# mrf89-breakout.net
KiCad netlist of a schematic drawn in EAGLE
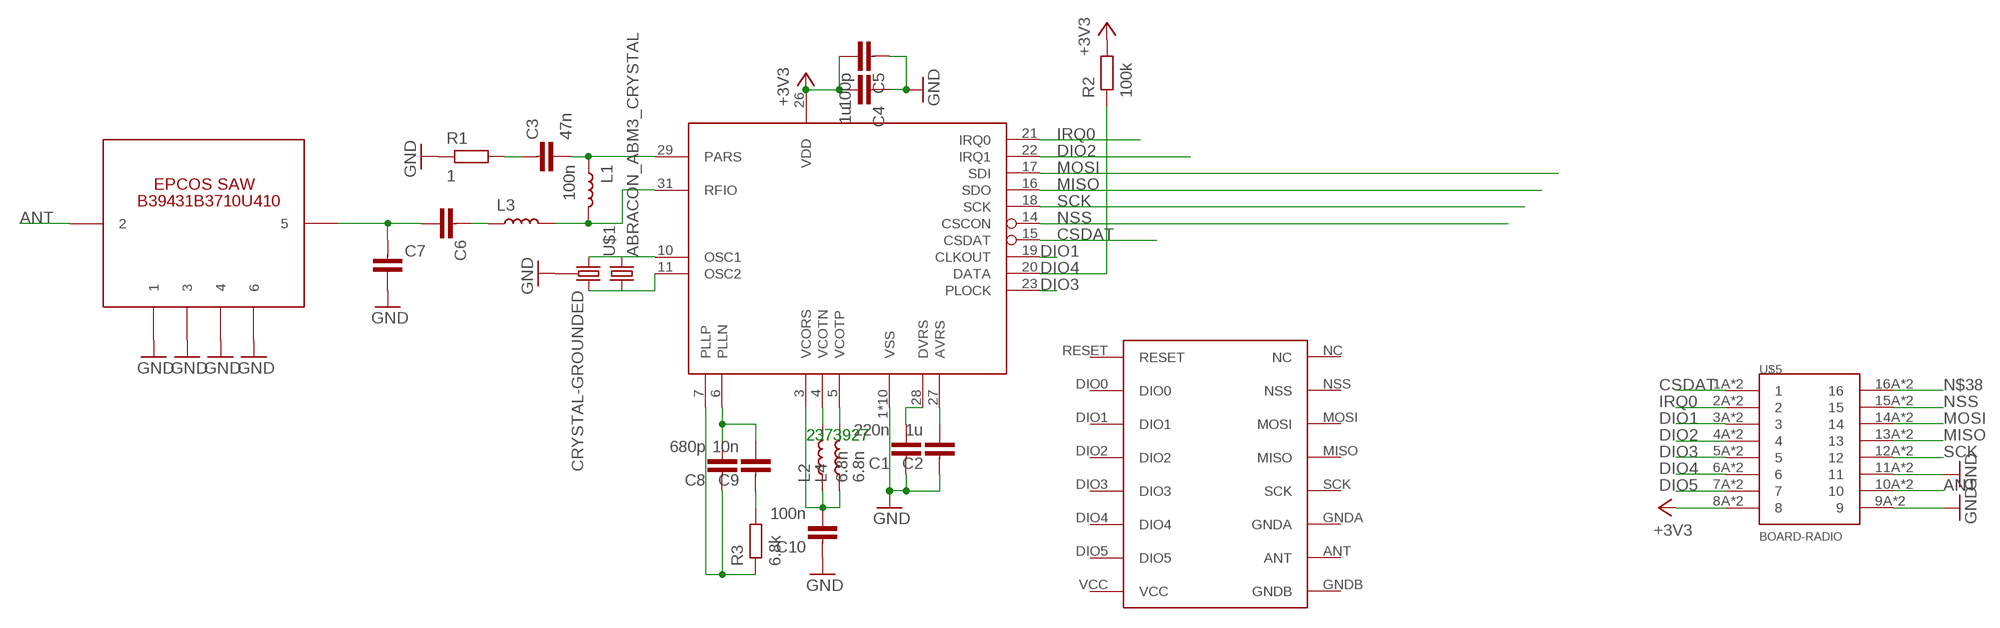
[diagram p0: schematic, sheet 1]

(export (version "E")
  (design (tool "Eeschema 10.0.6"))
  (components
    (comp (ref "C1")
      (value "220n")
      (footprint "eagle-import:C0603-N")
      (libsource (lib "eagle-import") (part "CAPACITOR0603-N"))
    )
    (comp (ref "C2")
      (value "1u")
      (footprint "eagle-import:C0603-N")
      (libsource (lib "eagle-import") (part "CAPACITOR0603-N"))
    )
    (comp (ref "C3")
      (value "47n")
      (footprint "eagle-import:C0603-N")
      (libsource (lib "eagle-import") (part "CAPACITOR0603-N"))
    )
    (comp (ref "C4")
      (value "1u")
      (footprint "eagle-import:C0603-N")
      (libsource (lib "eagle-import") (part "CAPACITOR0603-N"))
    )
    (comp (ref "C5")
      (value "100p")
      (footprint "eagle-import:C0603-N")
      (libsource (lib "eagle-import") (part "CAPACITOR0603-N"))
    )
    (comp (ref "C6")
      (value "CAPACITOR0603-N")
      (footprint "eagle-import:C0603-N")
      (libsource (lib "eagle-import") (part "CAPACITOR0603-N"))
    )
    (comp (ref "C7")
      (value "CAPACITOR0603-N")
      (footprint "eagle-import:C0603-N")
      (libsource (lib "eagle-import") (part "CAPACITOR0603-N"))
    )
    (comp (ref "C8")
      (value "680p")
      (footprint "eagle-import:C0603-N")
      (libsource (lib "eagle-import") (part "CAPACITOR0603-N"))
    )
    (comp (ref "C9")
      (value "10n")
      (footprint "eagle-import:C0603-N")
      (libsource (lib "eagle-import") (part "CAPACITOR0603-N"))
    )
    (comp (ref "C10")
      (value "100n")
      (footprint "eagle-import:C0603-N")
      (libsource (lib "eagle-import") (part "CAPACITOR0603-N"))
    )
    (comp (ref "IC1")
      (value "MRF89XA")
      (footprint "eagle-import:QFN32")
      (libsource (lib "eagle-import") (part "MRF89XA"))
    )
    (comp (ref "L1")
      (value "100n")
      (footprint "eagle-import:L0603-N")
      (libsource (lib "eagle-import") (part "INDUCTOR0603-N"))
    )
    (comp (ref "L2")
      (value "6.8n")
      (footprint "eagle-import:L0402-N")
      (libsource (lib "eagle-import") (part "INDUCTOR0402-N"))
    )
    (comp (ref "L3")
      (value "INDUCTOR0402-N")
      (footprint "eagle-import:L0402-N")
      (libsource (lib "eagle-import") (part "INDUCTOR0402-N"))
    )
    (comp (ref "L4")
      (value "6.8n")
      (footprint "eagle-import:L0402-N")
      (libsource (lib "eagle-import") (part "INDUCTOR0402-N"))
    )
    (comp (ref "R1")
      (value "1")
      (footprint "eagle-import:R0603-N")
      (libsource (lib "eagle-import") (part "RESISTOR0603-N"))
    )
    (comp (ref "R2")
      (value "100k")
      (footprint "eagle-import:R0603-N")
      (libsource (lib "eagle-import") (part "RESISTOR0603-N"))
    )
    (comp (ref "R3")
      (value "6.8k")
      (footprint "eagle-import:R0603-N")
      (libsource (lib "eagle-import") (part "RESISTOR0603-N"))
    )
    (comp (ref "U$1")
      (value "ABRACON_ABM3_CRYSTAL")
      (footprint "eagle-import:ABRACON_ABM3_CRYSTAL")
      (libsource (lib "eagle-import") (part "ABRACON_ABM3_CRYSTAL"))
    )
    (comp (ref "U$2")
      (value "EPCOS_SAW_FILTER")
      (footprint "eagle-import:EPCOS_SAW_FILTER")
      (libsource (lib "eagle-import") (part "EPCOS_SAW_FILTER"))
    )
    (comp (ref "U$3")
      (value "RFM69HW")
      (footprint "eagle-import:RFM")
      (libsource (lib "eagle-import") (part "RFM69HW"))
    )
    (comp (ref "U$4")
      (value "CRYSTAL-GROUNDED")
      (footprint "eagle-import:CRYSTAL-SMD-5X3")
      (libsource (lib "eagle-import") (part "CRYSTAL-GROUNDED"))
    )
    (comp (ref "U$5")
      (value "BOARD-RADIO")
      (footprint "eagle-import:BOARD-RADIO")
      (libsource (lib "eagle-import") (part "BOARD-RADIO"))
    )
  )
  (nets
    (net (code "1") (name "+3V3") (class "Default")
      (node (ref "C4") (pin "2") (pinfunction "2_2") (pintype "passive"))
      (node (ref "C5") (pin "2") (pinfunction "2_2") (pintype "passive"))
      (node (ref "IC1") (pin "26") (pinfunction "VDD_26") (pintype "power_in"))
      (node (ref "R2") (pin "2") (pinfunction "P$2_2") (pintype "passive"))
      (node (ref "U$5") (pin "8A") (pinfunction "8_8A") (pintype "passive"))
      (node (ref "U$5") (pin "8B") (pinfunction "8_8B") (pintype "passive"))
    )
    (net (code "2") (name "/ANT") (class "Default")
      (node (ref "U$2") (pin "P$2") (pinfunction "2_P$2") (pintype "bidirectional"))
      (node (ref "U$5") (pin "10A") (pinfunction "10_10A") (pintype "passive"))
      (node (ref "U$5") (pin "10B") (pinfunction "10_10B") (pintype "passive"))
    )
    (net (code "3") (name "/CSDAT") (class "Default")
      (node (ref "IC1") (pin "15") (pinfunction "CSDAT_15") (pintype "input"))
      (node (ref "U$5") (pin "1A") (pinfunction "1_1A") (pintype "passive"))
      (node (ref "U$5") (pin "1B") (pinfunction "1_1B") (pintype "passive"))
    )
    (net (code "4") (name "/DIO1") (class "Default")
      (node (ref "IC1") (pin "19") (pinfunction "CLKOUT_19") (pintype "output"))
      (node (ref "U$5") (pin "3A") (pinfunction "3_3A") (pintype "passive"))
      (node (ref "U$5") (pin "3B") (pinfunction "3_3B") (pintype "passive"))
    )
    (net (code "5") (name "/DIO2") (class "Default")
      (node (ref "IC1") (pin "22") (pinfunction "IRQ1_22") (pintype "output"))
      (node (ref "U$5") (pin "4A") (pinfunction "4_4A") (pintype "passive"))
      (node (ref "U$5") (pin "4B") (pinfunction "4_4B") (pintype "passive"))
    )
    (net (code "6") (name "/DIO3") (class "Default")
      (node (ref "IC1") (pin "23") (pinfunction "PLOCK_23") (pintype "output"))
      (node (ref "U$5") (pin "5A") (pinfunction "5_5A") (pintype "passive"))
      (node (ref "U$5") (pin "5B") (pinfunction "5_5B") (pintype "passive"))
    )
    (net (code "7") (name "/DIO4") (class "Default")
      (node (ref "IC1") (pin "20") (pinfunction "DATA_20") (pintype "bidirectional"))
      (node (ref "R2") (pin "1") (pinfunction "P$1_1") (pintype "passive"))
      (node (ref "U$5") (pin "6A") (pinfunction "6_6A") (pintype "passive"))
      (node (ref "U$5") (pin "6B") (pinfunction "6_6B") (pintype "passive"))
    )
    (net (code "8") (name "/DIO5") (class "Default")
      (node (ref "U$5") (pin "7A") (pinfunction "7_7A") (pintype "passive"))
      (node (ref "U$5") (pin "7B") (pinfunction "7_7B") (pintype "passive"))
    )
    (net (code "9") (name "/IRQ0") (class "Default")
      (node (ref "IC1") (pin "21") (pinfunction "IRQ0_21") (pintype "output"))
      (node (ref "U$5") (pin "2A") (pinfunction "2_2A") (pintype "passive"))
      (node (ref "U$5") (pin "2B") (pinfunction "2_2B") (pintype "passive"))
    )
    (net (code "10") (name "/MISO") (class "Default")
      (node (ref "IC1") (pin "16") (pinfunction "SDO_16") (pintype "output"))
      (node (ref "U$5") (pin "13A") (pinfunction "13_13A") (pintype "passive"))
      (node (ref "U$5") (pin "13B") (pinfunction "13_13B") (pintype "passive"))
    )
    (net (code "11") (name "/MOSI") (class "Default")
      (node (ref "IC1") (pin "17") (pinfunction "SDI_17") (pintype "input"))
      (node (ref "U$5") (pin "14A") (pinfunction "14_14A") (pintype "passive"))
      (node (ref "U$5") (pin "14B") (pinfunction "14_14B") (pintype "passive"))
    )
    (net (code "12") (name "/N$38") (class "Default")
      (node (ref "U$5") (pin "16A") (pinfunction "16_16A") (pintype "passive"))
      (node (ref "U$5") (pin "16B") (pinfunction "16_16B") (pintype "passive"))
    )
    (net (code "13") (name "/NSS") (class "Default")
      (node (ref "IC1") (pin "14") (pinfunction "CSCON_14") (pintype "input"))
      (node (ref "U$5") (pin "15A") (pinfunction "15_15A") (pintype "passive"))
      (node (ref "U$5") (pin "15B") (pinfunction "15_15B") (pintype "passive"))
    )
    (net (code "14") (name "/SCK") (class "Default")
      (node (ref "IC1") (pin "18") (pinfunction "SCK_18") (pintype "input"))
      (node (ref "U$5") (pin "12A") (pinfunction "12_12A") (pintype "passive"))
      (node (ref "U$5") (pin "12B") (pinfunction "12_12B") (pintype "passive"))
    )
    (net (code "15") (name "GND") (class "Default")
      (node (ref "C1") (pin "1") (pinfunction "1_1") (pintype "passive"))
      (node (ref "C10") (pin "1") (pinfunction "1_1") (pintype "passive"))
      (node (ref "C2") (pin "1") (pinfunction "1_1") (pintype "passive"))
      (node (ref "C4") (pin "1") (pinfunction "1_1") (pintype "passive"))
      (node (ref "C5") (pin "1") (pinfunction "1_1") (pintype "passive"))
      (node (ref "C7") (pin "2") (pinfunction "2_2") (pintype "passive"))
      (node (ref "IC1") (pin "1") (pinfunction "VSS_1") (pintype "power_in"))
      (node (ref "IC1") (pin "12") (pinfunction "VSS_12") (pintype "power_in"))
      (node (ref "IC1") (pin "2") (pinfunction "VSS_2") (pintype "power_in"))
      (node (ref "IC1") (pin "24") (pinfunction "VSS_24") (pintype "power_in"))
      (node (ref "IC1") (pin "25") (pinfunction "VSS_25") (pintype "power_in"))
      (node (ref "IC1") (pin "30") (pinfunction "VSS_30") (pintype "power_in"))
      (node (ref "IC1") (pin "32") (pinfunction "VSS_32") (pintype "power_in"))
      (node (ref "IC1") (pin "8") (pinfunction "VSS_8") (pintype "power_in"))
      (node (ref "IC1") (pin "9") (pinfunction "VSS_9") (pintype "power_in"))
      (node (ref "IC1") (pin "EXP") (pinfunction "VSS_EXP") (pintype "power_in"))
      (node (ref "R1") (pin "1") (pinfunction "P$1_1") (pintype "passive"))
      (node (ref "U$2") (pin "P$1") (pinfunction "1_P$1") (pintype "bidirectional"))
      (node (ref "U$2") (pin "P$3") (pinfunction "3_P$3") (pintype "bidirectional"))
      (node (ref "U$2") (pin "P$4") (pinfunction "4_P$4") (pintype "bidirectional"))
      (node (ref "U$2") (pin "P$6") (pinfunction "6_P$6") (pintype "bidirectional"))
      (node (ref "U$4") (pin "2") (pinfunction "3_2") (pintype "passive"))
      (node (ref "U$4") (pin "4") (pinfunction "3_4") (pintype "passive"))
      (node (ref "U$5") (pin "11A") (pinfunction "11_11A") (pintype "passive"))
      (node (ref "U$5") (pin "11B") (pinfunction "11_11B") (pintype "passive"))
      (node (ref "U$5") (pin "9A") (pinfunction "9_9A") (pintype "passive"))
      (node (ref "U$5") (pin "9B") (pinfunction "9_9B") (pintype "passive"))
    )
    (net (code "16") (name "Net-(IC1-AVRS)") (class "Default")
      (node (ref "C2") (pin "2") (pinfunction "2_2") (pintype "passive"))
      (node (ref "IC1") (pin "27") (pinfunction "AVRS_27") (pintype "output"))
    )
    (net (code "17") (name "Net-(IC1-DVRS)") (class "Default")
      (node (ref "C1") (pin "2") (pinfunction "2_2") (pintype "passive"))
      (node (ref "IC1") (pin "28") (pinfunction "DVRS_28") (pintype "output"))
    )
    (net (code "18") (name "Net-(IC1-OSC1)") (class "Default")
      (node (ref "IC1") (pin "10") (pinfunction "OSC1_10") (pintype "input"))
      (node (ref "U$1") (pin "P$2") (pinfunction "2_P$2") (pintype "passive"))
      (node (ref "U$4") (pin "3") (pinfunction "1_3") (pintype "passive"))
    )
    (net (code "19") (name "Net-(IC1-OSC2)") (class "Default")
      (node (ref "IC1") (pin "11") (pinfunction "OSC2_11") (pintype "input"))
      (node (ref "U$1") (pin "P$1") (pinfunction "1_P$1") (pintype "passive"))
      (node (ref "U$4") (pin "1") (pinfunction "2_1") (pintype "passive"))
    )
    (net (code "20") (name "Net-(IC1-PARS)") (class "Default")
      (node (ref "C3") (pin "2") (pinfunction "2_2") (pintype "passive"))
      (node (ref "IC1") (pin "29") (pinfunction "PARS_29") (pintype "output"))
      (node (ref "L1") (pin "1") (pinfunction "P$1_1") (pintype "passive"))
    )
    (net (code "21") (name "Net-(IC1-PLLN)") (class "Default")
      (node (ref "C8") (pin "2") (pinfunction "2_2") (pintype "passive"))
      (node (ref "C9") (pin "2") (pinfunction "2_2") (pintype "passive"))
      (node (ref "IC1") (pin "6") (pinfunction "PLLN_6") (pintype "bidirectional"))
    )
    (net (code "22") (name "Net-(IC1-PLLP)") (class "Default")
      (node (ref "C8") (pin "1") (pinfunction "1_1") (pintype "passive"))
      (node (ref "IC1") (pin "7") (pinfunction "PLLP_7") (pintype "bidirectional"))
      (node (ref "R3") (pin "1") (pinfunction "P$1_1") (pintype "passive"))
    )
    (net (code "23") (name "Net-(IC1-RFIO)") (class "Default")
      (node (ref "IC1") (pin "31") (pinfunction "RFIO_31") (pintype "bidirectional"))
      (node (ref "L1") (pin "2") (pinfunction "P$2_2") (pintype "passive"))
      (node (ref "L3") (pin "2") (pinfunction "P$2_2") (pintype "passive"))
    )
    (net (code "24") (name "Net-(IC1-VCORS)") (class "Default")
      (node (ref "C10") (pin "2") (pinfunction "2_2") (pintype "passive"))
      (node (ref "IC1") (pin "3") (pinfunction "VCORS_3") (pintype "output"))
      (node (ref "L2") (pin "1") (pinfunction "P$1_1") (pintype "passive"))
      (node (ref "L4") (pin "1") (pinfunction "P$1_1") (pintype "passive"))
    )
    (net (code "25") (name "Net-(IC1-VCOTN)") (class "Default")
      (node (ref "IC1") (pin "4") (pinfunction "VCOTN_4") (pintype "bidirectional"))
      (node (ref "L2") (pin "2") (pinfunction "P$2_2") (pintype "passive"))
    )
    (net (code "26") (name "Net-(IC1-VCOTP)") (class "Default")
      (node (ref "IC1") (pin "5") (pinfunction "VCOTP_5") (pintype "bidirectional"))
      (node (ref "L4") (pin "2") (pinfunction "P$2_2") (pintype "passive"))
    )
    (net (code "27") (name "Net-(L3-P$1)") (class "Default")
      (node (ref "C6") (pin "1") (pinfunction "1_1") (pintype "passive"))
      (node (ref "L3") (pin "1") (pinfunction "P$1_1") (pintype "passive"))
    )
    (net (code "28") (name "Net-(R1-P$2)") (class "Default")
      (node (ref "C3") (pin "1") (pinfunction "1_1") (pintype "passive"))
      (node (ref "R1") (pin "2") (pinfunction "P$2_2") (pintype "passive"))
    )
    (net (code "29") (name "Net-(R3-P$2)") (class "Default")
      (node (ref "C9") (pin "1") (pinfunction "1_1") (pintype "passive"))
      (node (ref "R3") (pin "2") (pinfunction "P$2_2") (pintype "passive"))
    )
    (net (code "30") (name "Net-(U$2-5)") (class "Default")
      (node (ref "C6") (pin "2") (pinfunction "2_2") (pintype "passive"))
      (node (ref "C7") (pin "1") (pinfunction "1_1") (pintype "passive"))
      (node (ref "U$2") (pin "P$5") (pinfunction "5_P$5") (pintype "bidirectional"))
    )
    (net (code "31") (name "unconnected-(U$3-PadANT)") (class "Default")
      (node (ref "U$3") (pin "ANT") (pinfunction "ANT_ANT") (pintype "bidirectional"))
    )
    (net (code "32") (name "unconnected-(U$3-PadDIO0)") (class "Default")
      (node (ref "U$3") (pin "DIO0") (pinfunction "DIO0_DIO0") (pintype "bidirectional"))
    )
    (net (code "33") (name "unconnected-(U$3-PadDIO1)") (class "Default")
      (node (ref "U$3") (pin "DIO1") (pinfunction "DIO1_DIO1") (pintype "bidirectional"))
    )
    (net (code "34") (name "unconnected-(U$3-PadDIO2)") (class "Default")
      (node (ref "U$3") (pin "DIO2") (pinfunction "DIO2_DIO2") (pintype "bidirectional"))
    )
    (net (code "35") (name "unconnected-(U$3-PadDIO3)") (class "Default")
      (node (ref "U$3") (pin "DIO3") (pinfunction "DIO3_DIO3") (pintype "bidirectional"))
    )
    (net (code "36") (name "unconnected-(U$3-PadDIO4)") (class "Default")
      (node (ref "U$3") (pin "DIO4") (pinfunction "DIO4_DIO4") (pintype "bidirectional"))
    )
    (net (code "37") (name "unconnected-(U$3-PadDIO5)") (class "Default")
      (node (ref "U$3") (pin "DIO5") (pinfunction "DIO5_DIO5") (pintype "bidirectional"))
    )
    (net (code "38") (name "unconnected-(U$3-PadGNDA)") (class "Default")
      (node (ref "U$3") (pin "GNDA") (pinfunction "GNDA_GNDA") (pintype "bidirectional"))
    )
    (net (code "39") (name "unconnected-(U$3-PadGNDB)") (class "Default")
      (node (ref "U$3") (pin "GNDB") (pinfunction "GNDB_GNDB") (pintype "bidirectional"))
    )
    (net (code "40") (name "unconnected-(U$3-PadMISO)") (class "Default")
      (node (ref "U$3") (pin "MISO") (pinfunction "MISO_MISO") (pintype "bidirectional"))
    )
    (net (code "41") (name "unconnected-(U$3-PadMOSI)") (class "Default")
      (node (ref "U$3") (pin "MOSI") (pinfunction "MOSI_MOSI") (pintype "bidirectional"))
    )
    (net (code "42") (name "unconnected-(U$3-PadNC)") (class "Default")
      (node (ref "U$3") (pin "NC") (pinfunction "NC_NC") (pintype "bidirectional"))
    )
    (net (code "43") (name "unconnected-(U$3-PadNSS)") (class "Default")
      (node (ref "U$3") (pin "NSS") (pinfunction "NSS_NSS") (pintype "bidirectional"))
    )
    (net (code "44") (name "unconnected-(U$3-PadRESET)") (class "Default")
      (node (ref "U$3") (pin "RESET") (pinfunction "RESET_RESET") (pintype "bidirectional"))
    )
    (net (code "45") (name "unconnected-(U$3-PadSCK)") (class "Default")
      (node (ref "U$3") (pin "SCK") (pinfunction "SCK_SCK") (pintype "bidirectional"))
    )
    (net (code "46") (name "unconnected-(U$3-PadVCC)") (class "Default")
      (node (ref "U$3") (pin "VCC") (pinfunction "VCC_VCC") (pintype "bidirectional"))
    )
  )
)
